# main_board_v0001.net
KiCad netlist of a schematic drawn in EAGLE
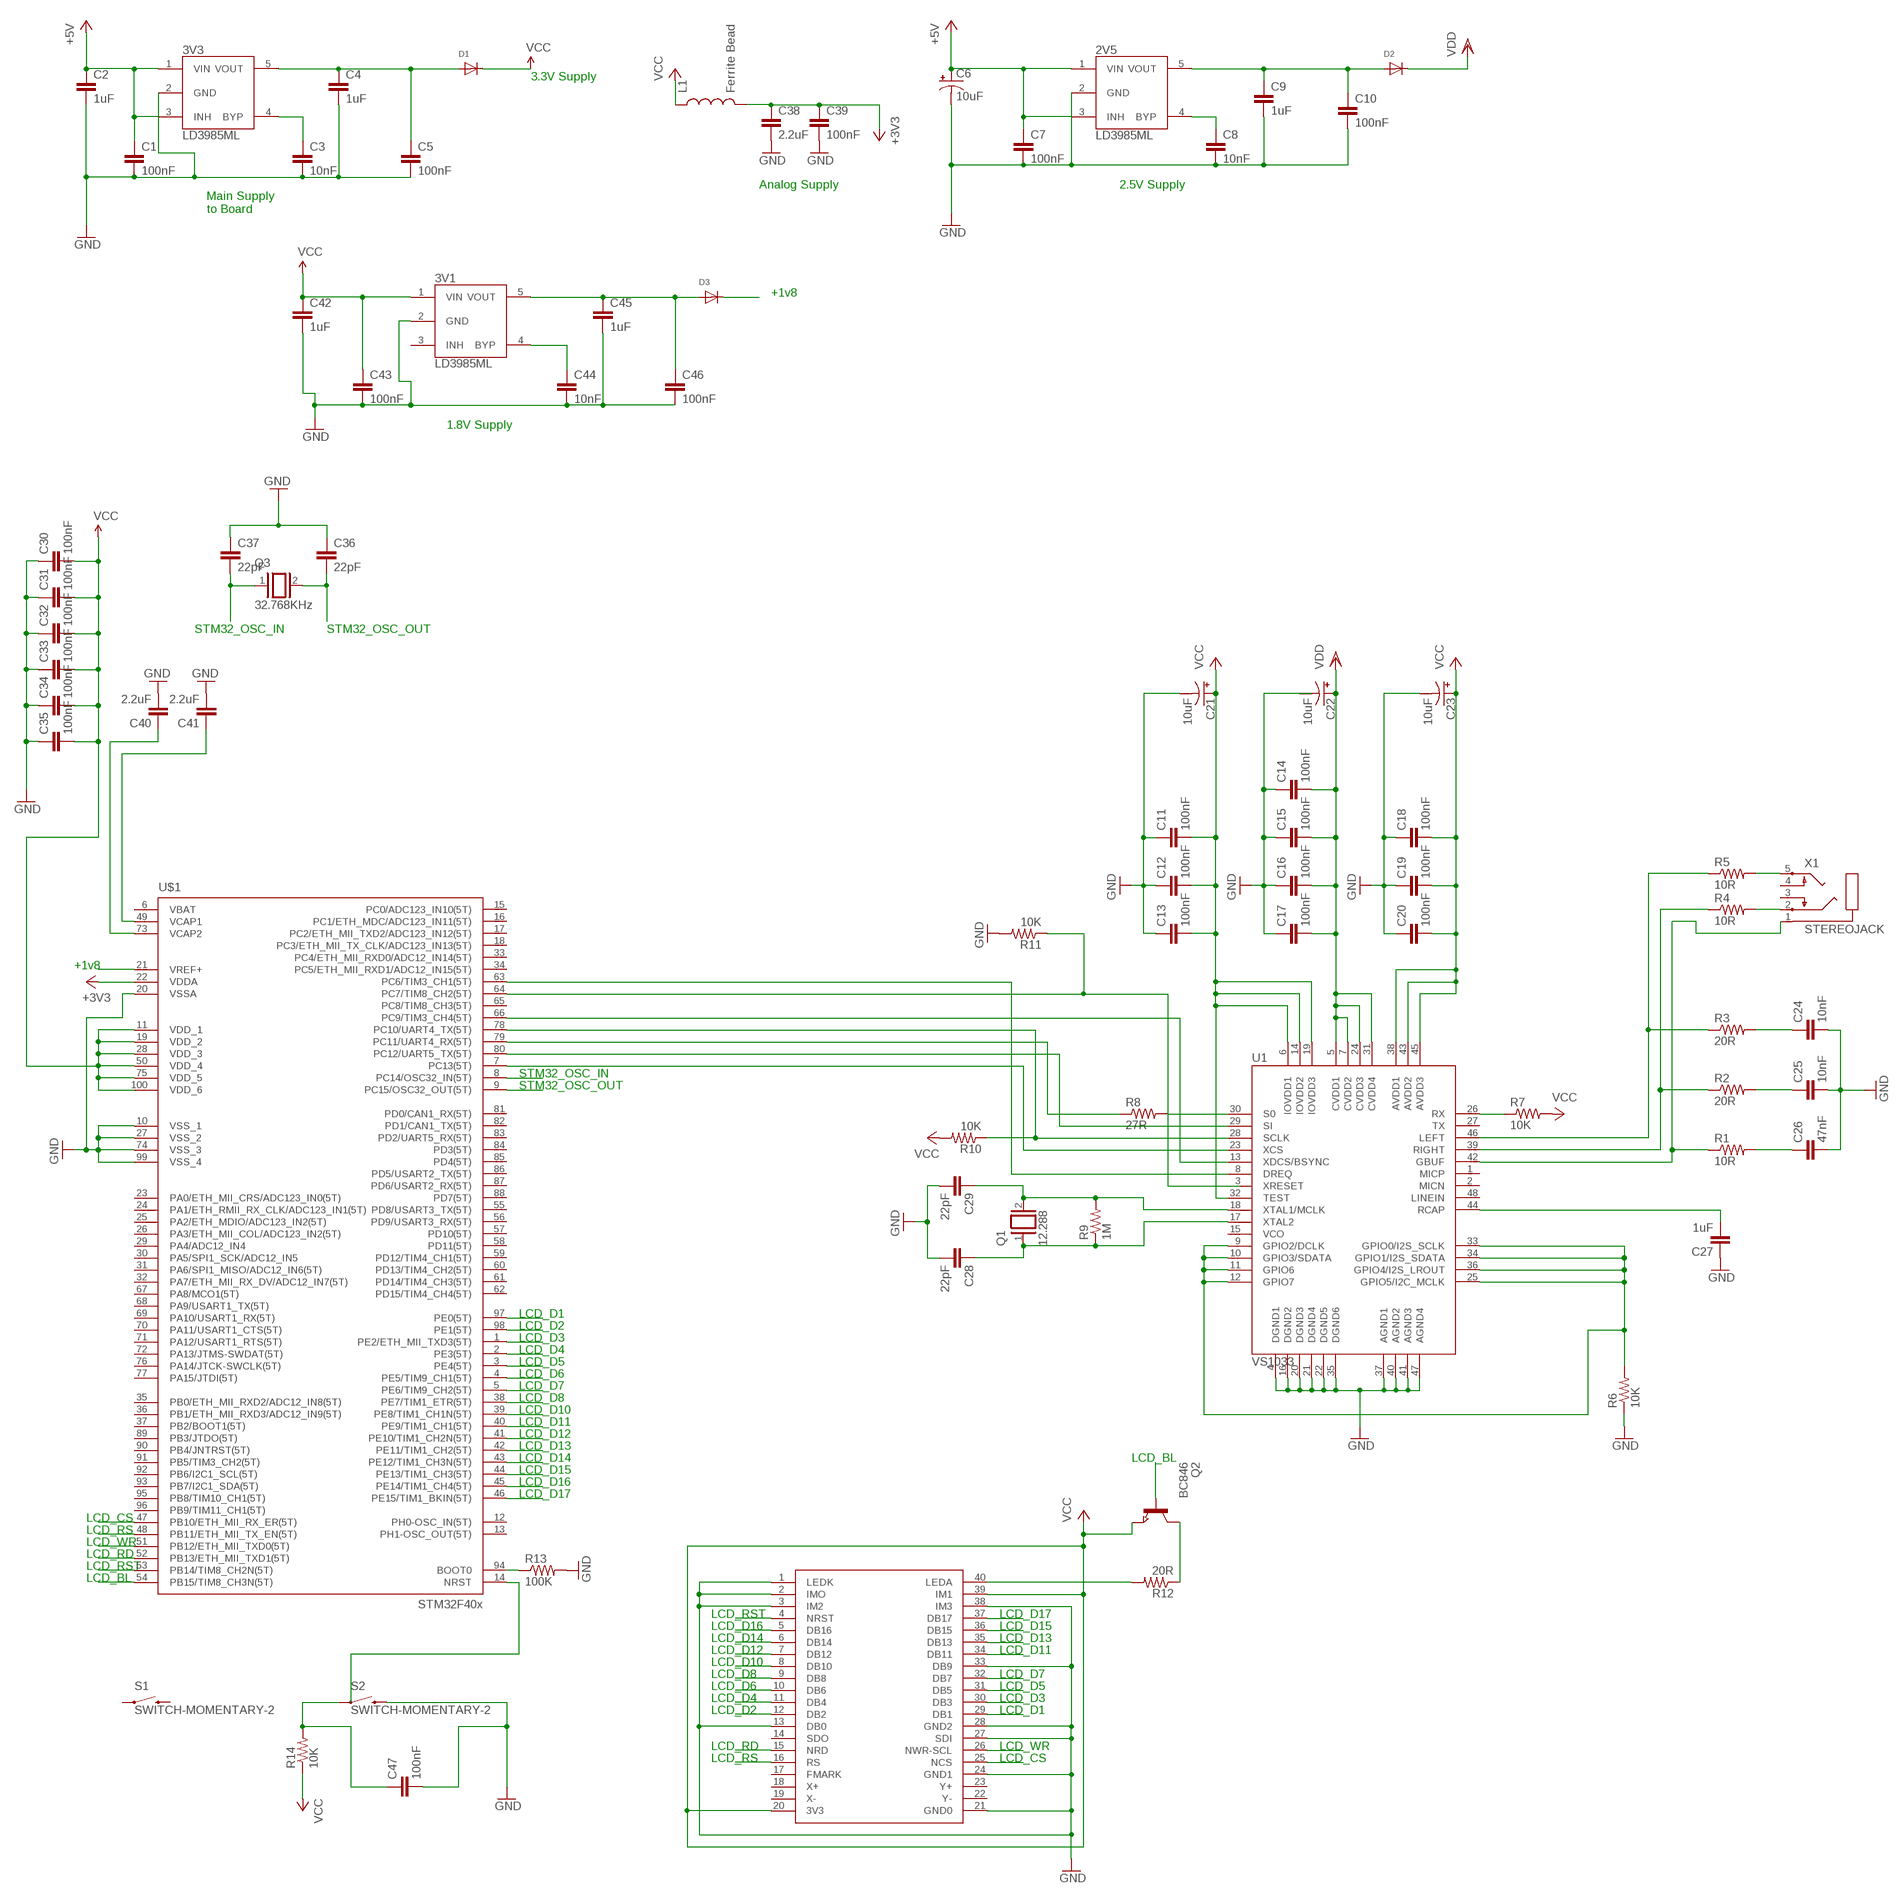
[diagram p0: schematic, sheet 1]

(export (version "E")
  (design (tool "Eeschema 10.0.6"))
  (components
    (comp (ref "2V5")
      (value "LD3985ML")
      (footprint "eagle-import:SOT-23-5L")
      (libsource (lib "eagle-import") (part "LD3985ML"))
    )
    (comp (ref "3V1")
      (value "LD3985ML")
      (footprint "eagle-import:SOT-23-5L")
      (libsource (lib "eagle-import") (part "LD3985ML"))
    )
    (comp (ref "3V3")
      (value "LD3985ML")
      (footprint "eagle-import:SOT-23-5L")
      (libsource (lib "eagle-import") (part "LD3985ML"))
    )
    (comp (ref "C1")
      (value "100nF")
      (footprint "eagle-import:C1005")
      (libsource (lib "eagle-import") (part "resistor_C-EUC1005"))
    )
    (comp (ref "C2")
      (value "1uF")
      (footprint "eagle-import:C0603")
      (libsource (lib "eagle-import") (part "C-EUC0603"))
    )
    (comp (ref "C3")
      (value "10nF")
      (footprint "eagle-import:C0603")
      (libsource (lib "eagle-import") (part "C-EUC0603"))
    )
    (comp (ref "C4")
      (value "1uF")
      (footprint "eagle-import:C0603")
      (libsource (lib "eagle-import") (part "C-EUC0603"))
    )
    (comp (ref "C5")
      (value "100nF")
      (footprint "eagle-import:C1005")
      (libsource (lib "eagle-import") (part "resistor_C-EUC1005"))
    )
    (comp (ref "C6")
      (value "10uF")
      (footprint "eagle-import:EIA3528-KIT")
      (libsource (lib "eagle-import") (part "CAP_POL3528-KIT"))
    )
    (comp (ref "C7")
      (value "100nF")
      (footprint "eagle-import:C1005")
      (libsource (lib "eagle-import") (part "resistor_C-EUC1005"))
    )
    (comp (ref "C8")
      (value "10nF")
      (footprint "eagle-import:C0603")
      (libsource (lib "eagle-import") (part "C-EUC0603"))
    )
    (comp (ref "C9")
      (value "1uF")
      (footprint "eagle-import:C0603")
      (libsource (lib "eagle-import") (part "C-EUC0603"))
    )
    (comp (ref "C10")
      (value "100nF")
      (footprint "eagle-import:C1005@1")
      (libsource (lib "eagle-import") (part "C-EUC1005"))
    )
    (comp (ref "C11")
      (value "100nF")
      (footprint "eagle-import:C0603")
      (libsource (lib "eagle-import") (part "C-EUC0603"))
    )
    (comp (ref "C12")
      (value "100nF")
      (footprint "eagle-import:C0603")
      (libsource (lib "eagle-import") (part "C-EUC0603"))
    )
    (comp (ref "C13")
      (value "100nF")
      (footprint "eagle-import:C0603")
      (libsource (lib "eagle-import") (part "C-EUC0603"))
    )
    (comp (ref "C14")
      (value "100nF")
      (footprint "eagle-import:C0603")
      (libsource (lib "eagle-import") (part "C-EUC0603"))
    )
    (comp (ref "C15")
      (value "100nF")
      (footprint "eagle-import:C0603")
      (libsource (lib "eagle-import") (part "C-EUC0603"))
    )
    (comp (ref "C16")
      (value "100nF")
      (footprint "eagle-import:C0603")
      (libsource (lib "eagle-import") (part "C-EUC0603"))
    )
    (comp (ref "C17")
      (value "100nF")
      (footprint "eagle-import:C0603")
      (libsource (lib "eagle-import") (part "C-EUC0603"))
    )
    (comp (ref "C18")
      (value "100nF")
      (footprint "eagle-import:C0603")
      (libsource (lib "eagle-import") (part "C-EUC0603"))
    )
    (comp (ref "C19")
      (value "100nF")
      (footprint "eagle-import:C0603")
      (libsource (lib "eagle-import") (part "C-EUC0603"))
    )
    (comp (ref "C20")
      (value "100nF")
      (footprint "eagle-import:C0603")
      (libsource (lib "eagle-import") (part "C-EUC0603"))
    )
    (comp (ref "C21")
      (value "10uF")
      (footprint "eagle-import:EIA3528-KIT")
      (libsource (lib "eagle-import") (part "CAP_POL3528-KIT"))
    )
    (comp (ref "C22")
      (value "10uF")
      (footprint "eagle-import:EIA3528-KIT")
      (libsource (lib "eagle-import") (part "CAP_POL3528-KIT"))
    )
    (comp (ref "C23")
      (value "10uF")
      (footprint "eagle-import:EIA3528-KIT")
      (libsource (lib "eagle-import") (part "CAP_POL3528-KIT"))
    )
    (comp (ref "C24")
      (value "10nF")
      (footprint "eagle-import:C0603")
      (libsource (lib "eagle-import") (part "C-EUC0603"))
    )
    (comp (ref "C25")
      (value "10nF")
      (footprint "eagle-import:C0603")
      (libsource (lib "eagle-import") (part "C-EUC0603"))
    )
    (comp (ref "C26")
      (value "47nF")
      (footprint "eagle-import:C0603")
      (libsource (lib "eagle-import") (part "C-EUC0603"))
    )
    (comp (ref "C27")
      (value "1uF")
      (footprint "eagle-import:C0603")
      (libsource (lib "eagle-import") (part "C-EUC0603"))
    )
    (comp (ref "C28")
      (value "22pF")
      (footprint "eagle-import:C0603")
      (libsource (lib "eagle-import") (part "C-EUC0603"))
    )
    (comp (ref "C29")
      (value "22pF")
      (footprint "eagle-import:C0603")
      (libsource (lib "eagle-import") (part "C-EUC0603"))
    )
    (comp (ref "C30")
      (value "100nF")
      (footprint "eagle-import:C1005")
      (libsource (lib "eagle-import") (part "resistor_C-EUC1005"))
    )
    (comp (ref "C31")
      (value "100nF")
      (footprint "eagle-import:C1005")
      (libsource (lib "eagle-import") (part "resistor_C-EUC1005"))
    )
    (comp (ref "C32")
      (value "100nF")
      (footprint "eagle-import:C1005")
      (libsource (lib "eagle-import") (part "resistor_C-EUC1005"))
    )
    (comp (ref "C33")
      (value "100nF")
      (footprint "eagle-import:C1005")
      (libsource (lib "eagle-import") (part "resistor_C-EUC1005"))
    )
    (comp (ref "C34")
      (value "100nF")
      (footprint "eagle-import:C1005")
      (libsource (lib "eagle-import") (part "resistor_C-EUC1005"))
    )
    (comp (ref "C35")
      (value "100nF")
      (footprint "eagle-import:C1005")
      (libsource (lib "eagle-import") (part "resistor_C-EUC1005"))
    )
    (comp (ref "C36")
      (value "22pF")
      (footprint "eagle-import:C1005")
      (libsource (lib "eagle-import") (part "resistor_C-EUC1005"))
    )
    (comp (ref "C37")
      (value "22pF")
      (footprint "eagle-import:C1005")
      (libsource (lib "eagle-import") (part "resistor_C-EUC1005"))
    )
    (comp (ref "C38")
      (value "2.2uF")
      (footprint "eagle-import:C1005")
      (libsource (lib "eagle-import") (part "resistor_C-EUC1005"))
    )
    (comp (ref "C39")
      (value "100nF")
      (footprint "eagle-import:C1005")
      (libsource (lib "eagle-import") (part "resistor_C-EUC1005"))
    )
    (comp (ref "C40")
      (value "2.2uF")
      (footprint "eagle-import:C1005")
      (libsource (lib "eagle-import") (part "resistor_C-EUC1005"))
    )
    (comp (ref "C41")
      (value "2.2uF")
      (footprint "eagle-import:C1005")
      (libsource (lib "eagle-import") (part "resistor_C-EUC1005"))
    )
    (comp (ref "C42")
      (value "1uF")
      (footprint "eagle-import:C0603")
      (libsource (lib "eagle-import") (part "C-EUC0603"))
    )
    (comp (ref "C43")
      (value "100nF")
      (footprint "eagle-import:C1005")
      (libsource (lib "eagle-import") (part "resistor_C-EUC1005"))
    )
    (comp (ref "C44")
      (value "10nF")
      (footprint "eagle-import:C0603")
      (libsource (lib "eagle-import") (part "C-EUC0603"))
    )
    (comp (ref "C45")
      (value "1uF")
      (footprint "eagle-import:C0603")
      (libsource (lib "eagle-import") (part "C-EUC0603"))
    )
    (comp (ref "C46")
      (value "100nF")
      (footprint "eagle-import:C1005")
      (libsource (lib "eagle-import") (part "resistor_C-EUC1005"))
    )
    (comp (ref "C47")
      (value "100nF")
      (footprint "eagle-import:C0603")
      (libsource (lib "eagle-import") (part "C-EUC0603"))
    )
    (comp (ref "D1")
      (value "DIODESOD-323F")
      (footprint "eagle-import:SOD-323F")
      (libsource (lib "eagle-import") (part "DIODESOD-323F"))
    )
    (comp (ref "D2")
      (value "DIODESOD-323F")
      (footprint "eagle-import:SOD-323F")
      (libsource (lib "eagle-import") (part "DIODESOD-323F"))
    )
    (comp (ref "D3")
      (value "DIODESOD-323F")
      (footprint "eagle-import:SOD-323F")
      (libsource (lib "eagle-import") (part "DIODESOD-323F"))
    )
    (comp (ref "L1")
      (value "Ferrite Bead")
      (footprint "eagle-import:C0402")
      (libsource (lib "eagle-import") (part "INDUCTOR0402"))
    )
    (comp (ref "Q1")
      (value "12.288")
      (footprint "eagle-import:QS")
      (libsource (lib "eagle-import") (part "XTAL/S"))
    )
    (comp (ref "Q2")
      (value "BC846")
      (footprint "eagle-import:SOT23")
      (libsource (lib "eagle-import") (part "NPN-TRANSISTOR_SOT23"))
    )
    (comp (ref "Q3")
      (value "32.768KHz")
      (footprint "eagle-import:QS")
      (libsource (lib "eagle-import") (part "XTAL/S"))
    )
    (comp (ref "R1")
      (value "10R")
      (footprint "eagle-import:M0805")
      (libsource (lib "eagle-import") (part "R-US_M0805"))
    )
    (comp (ref "R2")
      (value "20R")
      (footprint "eagle-import:M0805")
      (libsource (lib "eagle-import") (part "R-US_M0805"))
    )
    (comp (ref "R3")
      (value "20R")
      (footprint "eagle-import:M0805")
      (libsource (lib "eagle-import") (part "R-US_M0805"))
    )
    (comp (ref "R4")
      (value "10R")
      (footprint "eagle-import:M0805")
      (libsource (lib "eagle-import") (part "R-US_M0805"))
    )
    (comp (ref "R5")
      (value "10R")
      (footprint "eagle-import:M0805")
      (libsource (lib "eagle-import") (part "R-US_M0805"))
    )
    (comp (ref "R6")
      (value "10K")
      (footprint "eagle-import:M0805")
      (libsource (lib "eagle-import") (part "R-US_M0805"))
    )
    (comp (ref "R7")
      (value "10K")
      (footprint "eagle-import:M0805")
      (libsource (lib "eagle-import") (part "R-US_M0805"))
    )
    (comp (ref "R8")
      (value "27R")
      (footprint "eagle-import:M0805")
      (libsource (lib "eagle-import") (part "R-US_M0805"))
    )
    (comp (ref "R9")
      (value "1M")
      (footprint "eagle-import:M0805")
      (libsource (lib "eagle-import") (part "R-US_M0805"))
    )
    (comp (ref "R10")
      (value "10K")
      (footprint "eagle-import:M0805")
      (libsource (lib "eagle-import") (part "R-US_M0805"))
    )
    (comp (ref "R11")
      (value "10K")
      (footprint "eagle-import:M0805")
      (libsource (lib "eagle-import") (part "R-US_M0805"))
    )
    (comp (ref "R12")
      (value "20R")
      (footprint "eagle-import:M0805")
      (libsource (lib "eagle-import") (part "R-US_M0805"))
    )
    (comp (ref "R13")
      (value "100K")
      (footprint "eagle-import:M0805")
      (libsource (lib "eagle-import") (part "R-US_M0805"))
    )
    (comp (ref "R14")
      (value "10K")
      (footprint "eagle-import:M0805")
      (libsource (lib "eagle-import") (part "R-US_M0805"))
    )
    (comp (ref "S1")
      (value "SWITCH-MOMENTARY-2")
      (footprint "eagle-import:TACTILE_SWITCH_TALL")
      (libsource (lib "eagle-import") (part "SWITCH-MOMENTARY-2"))
    )
    (comp (ref "S2")
      (value "SWITCH-MOMENTARY-2")
      (footprint "eagle-import:TACTILE_SWITCH_TALL")
      (libsource (lib "eagle-import") (part "SWITCH-MOMENTARY-2"))
    )
    (comp (ref "U$1")
      (value "STM32F407V")
      (footprint "eagle-import:TQFP100")
      (libsource (lib "eagle-import") (part "STM32F407V"))
    )
    (comp (ref "U$2")
      (value "MIKROE-PROTO-ILI9341")
      (footprint "eagle-import:2X20-PINHEAD")
      (libsource (lib "eagle-import") (part "MIKROE-PROTO-ILI9341"))
    )
    (comp (ref "U1")
      (value "VS1033")
      (footprint "eagle-import:LQFP-48")
      (libsource (lib "eagle-import") (part "VS1033"))
    )
    (comp (ref "X1")
      (value "STEREOJACK")
      (footprint "eagle-import:STX3100")
      (libsource (lib "eagle-import") (part "STEREOJACK"))
    )
  )
  (nets
    (net (code "1") (name "+3V3") (class "Default")
      (node (ref "C38") (pin "1") (pinfunction "1_1") (pintype "passive"))
      (node (ref "C39") (pin "1") (pinfunction "1_1") (pintype "passive"))
      (node (ref "L1") (pin "2") (pinfunction "2_2") (pintype "passive"))
      (node (ref "U$1") (pin "22") (pinfunction "VDDA_22") (pintype "bidirectional"))
    )
    (net (code "2") (name "+5V") (class "Default")
      (node (ref "2V5") (pin "1") (pinfunction "VIN_1") (pintype "bidirectional"))
      (node (ref "2V5") (pin "3") (pinfunction "INH_3") (pintype "bidirectional"))
      (node (ref "3V3") (pin "1") (pinfunction "VIN_1") (pintype "bidirectional"))
      (node (ref "3V3") (pin "3") (pinfunction "INH_3") (pintype "bidirectional"))
      (node (ref "C1") (pin "1") (pinfunction "1_1") (pintype "passive"))
      (node (ref "C2") (pin "1") (pinfunction "1_1") (pintype "passive"))
      (node (ref "C6") (pin "A") (pinfunction "+_A") (pintype "passive"))
      (node (ref "C7") (pin "1") (pinfunction "1_1") (pintype "passive"))
    )
    (net (code "3") (name "/+1V8") (class "Default")
      (node (ref "D3") (pin "C") (pinfunction "C_C") (pintype "passive"))
      (node (ref "U$1") (pin "21") (pinfunction "VREF+_21") (pintype "bidirectional"))
    )
    (net (code "4") (name "/LCD_BL") (class "Default")
      (node (ref "Q2") (pin "1") (pinfunction "B_1") (pintype "passive"))
      (node (ref "U$1") (pin "54") (pinfunction "PB15/TIM8_CH3N(5T)_54") (pintype "bidirectional"))
    )
    (net (code "5") (name "/LCD_CS") (class "Default")
      (node (ref "U$1") (pin "47") (pinfunction "PB10/ETH_MII_RX_ER(5T)_47") (pintype "bidirectional"))
      (node (ref "U$2") (pin "25") (pinfunction "NCS_25") (pintype "bidirectional"))
    )
    (net (code "6") (name "/LCD_D1") (class "Default")
      (node (ref "U$1") (pin "97") (pinfunction "PE0(5T)_97") (pintype "bidirectional"))
      (node (ref "U$2") (pin "29") (pinfunction "DB1_29") (pintype "bidirectional"))
    )
    (net (code "7") (name "/LCD_D2") (class "Default")
      (node (ref "U$1") (pin "98") (pinfunction "PE1(5T)_98") (pintype "bidirectional"))
      (node (ref "U$2") (pin "12") (pinfunction "DB2_12") (pintype "bidirectional"))
    )
    (net (code "8") (name "/LCD_D3") (class "Default")
      (node (ref "U$1") (pin "1") (pinfunction "PE2/ETH_MII_TXD3(5T)_1") (pintype "bidirectional"))
      (node (ref "U$2") (pin "30") (pinfunction "DB3_30") (pintype "bidirectional"))
    )
    (net (code "9") (name "/LCD_D4") (class "Default")
      (node (ref "U$1") (pin "2") (pinfunction "PE3(5T)_2") (pintype "bidirectional"))
      (node (ref "U$2") (pin "11") (pinfunction "DB4_11") (pintype "bidirectional"))
    )
    (net (code "10") (name "/LCD_D5") (class "Default")
      (node (ref "U$1") (pin "3") (pinfunction "PE4(5T)_3") (pintype "bidirectional"))
      (node (ref "U$2") (pin "31") (pinfunction "DB5_31") (pintype "bidirectional"))
    )
    (net (code "11") (name "/LCD_D6") (class "Default")
      (node (ref "U$1") (pin "4") (pinfunction "PE5/TIM9_CH1(5T)_4") (pintype "bidirectional"))
      (node (ref "U$2") (pin "10") (pinfunction "DB6_10") (pintype "bidirectional"))
    )
    (net (code "12") (name "/LCD_D7") (class "Default")
      (node (ref "U$1") (pin "5") (pinfunction "PE6/TIM9_CH2(5T)_5") (pintype "bidirectional"))
      (node (ref "U$2") (pin "32") (pinfunction "DB7_32") (pintype "bidirectional"))
    )
    (net (code "13") (name "/LCD_D8") (class "Default")
      (node (ref "U$1") (pin "38") (pinfunction "PE7/TIM1_ETR(5T)_38") (pintype "bidirectional"))
      (node (ref "U$2") (pin "9") (pinfunction "DB8_9") (pintype "bidirectional"))
    )
    (net (code "14") (name "/LCD_D10") (class "Default")
      (node (ref "U$1") (pin "39") (pinfunction "PE8/TIM1_CH1N(5T)_39") (pintype "bidirectional"))
      (node (ref "U$2") (pin "8") (pinfunction "DB10_8") (pintype "bidirectional"))
    )
    (net (code "15") (name "/LCD_D11") (class "Default")
      (node (ref "U$1") (pin "40") (pinfunction "PE9/TIM1_CH1(5T)_40") (pintype "bidirectional"))
      (node (ref "U$2") (pin "34") (pinfunction "DB11_34") (pintype "bidirectional"))
    )
    (net (code "16") (name "/LCD_D12") (class "Default")
      (node (ref "U$1") (pin "41") (pinfunction "PE10/TIM1_CH2N(5T)_41") (pintype "bidirectional"))
      (node (ref "U$2") (pin "7") (pinfunction "DB12_7") (pintype "bidirectional"))
    )
    (net (code "17") (name "/LCD_D13") (class "Default")
      (node (ref "U$1") (pin "42") (pinfunction "PE11/TIM1_CH2(5T)_42") (pintype "bidirectional"))
      (node (ref "U$2") (pin "35") (pinfunction "DB13_35") (pintype "bidirectional"))
    )
    (net (code "18") (name "/LCD_D14") (class "Default")
      (node (ref "U$1") (pin "43") (pinfunction "PE12/TIM1_CH3N(5T)_43") (pintype "bidirectional"))
      (node (ref "U$2") (pin "6") (pinfunction "DB14_6") (pintype "bidirectional"))
    )
    (net (code "19") (name "/LCD_D15") (class "Default")
      (node (ref "U$1") (pin "44") (pinfunction "PE13/TIM1_CH3(5T)_44") (pintype "bidirectional"))
      (node (ref "U$2") (pin "36") (pinfunction "DB15_36") (pintype "bidirectional"))
    )
    (net (code "20") (name "/LCD_D16") (class "Default")
      (node (ref "U$1") (pin "45") (pinfunction "PE14/TIM1_CH4(5T)_45") (pintype "bidirectional"))
      (node (ref "U$2") (pin "5") (pinfunction "DB16_5") (pintype "bidirectional"))
    )
    (net (code "21") (name "/LCD_D17") (class "Default")
      (node (ref "U$1") (pin "46") (pinfunction "PE15/TIM1_BKIN(5T)_46") (pintype "bidirectional"))
      (node (ref "U$2") (pin "37") (pinfunction "DB17_37") (pintype "bidirectional"))
    )
    (net (code "22") (name "/LCD_RD") (class "Default")
      (node (ref "U$1") (pin "52") (pinfunction "PB13/ETH_MII_TXD1(5T)_52") (pintype "bidirectional"))
      (node (ref "U$2") (pin "15") (pinfunction "NRD_15") (pintype "bidirectional"))
    )
    (net (code "23") (name "/LCD_RS") (class "Default")
      (node (ref "U$1") (pin "48") (pinfunction "PB11/ETH_MII_TX_EN(5T)_48") (pintype "bidirectional"))
      (node (ref "U$2") (pin "16") (pinfunction "RS_16") (pintype "bidirectional"))
    )
    (net (code "24") (name "/LCD_RST") (class "Default")
      (node (ref "U$1") (pin "53") (pinfunction "PB14/TIM8_CH2N(5T)_53") (pintype "bidirectional"))
      (node (ref "U$2") (pin "4") (pinfunction "NRST_4") (pintype "bidirectional"))
    )
    (net (code "25") (name "/LCD_WR") (class "Default")
      (node (ref "U$1") (pin "51") (pinfunction "PB12/ETH_MII_TXD0(5T)_51") (pintype "bidirectional"))
      (node (ref "U$2") (pin "26") (pinfunction "NWR-SCL_26") (pintype "bidirectional"))
    )
    (net (code "26") (name "/STM32_OSC_IN") (class "Default")
      (node (ref "C37") (pin "2") (pinfunction "2_2") (pintype "passive"))
      (node (ref "Q3") (pin "1") (pinfunction "1_1") (pintype "passive"))
      (node (ref "U$1") (pin "8") (pinfunction "PC14/OSC32_IN(5T)_8") (pintype "bidirectional"))
    )
    (net (code "27") (name "/STM32_OSC_OUT") (class "Default")
      (node (ref "C36") (pin "2") (pinfunction "2_2") (pintype "passive"))
      (node (ref "Q3") (pin "2") (pinfunction "2_2") (pintype "passive"))
      (node (ref "U$1") (pin "9") (pinfunction "PC15/OSC32_OUT(5T)_9") (pintype "bidirectional"))
    )
    (net (code "28") (name "GND") (class "Default")
      (node (ref "2V5") (pin "2") (pinfunction "GND_2") (pintype "bidirectional"))
      (node (ref "3V1") (pin "2") (pinfunction "GND_2") (pintype "bidirectional"))
      (node (ref "3V3") (pin "2") (pinfunction "GND_2") (pintype "bidirectional"))
      (node (ref "C1") (pin "2") (pinfunction "2_2") (pintype "passive"))
      (node (ref "C10") (pin "2") (pinfunction "2_2") (pintype "passive"))
      (node (ref "C11") (pin "1") (pinfunction "1_1") (pintype "passive"))
      (node (ref "C12") (pin "1") (pinfunction "1_1") (pintype "passive"))
      (node (ref "C13") (pin "1") (pinfunction "1_1") (pintype "passive"))
      (node (ref "C14") (pin "1") (pinfunction "1_1") (pintype "passive"))
      (node (ref "C15") (pin "1") (pinfunction "1_1") (pintype "passive"))
      (node (ref "C16") (pin "1") (pinfunction "1_1") (pintype "passive"))
      (node (ref "C17") (pin "1") (pinfunction "1_1") (pintype "passive"))
      (node (ref "C18") (pin "1") (pinfunction "1_1") (pintype "passive"))
      (node (ref "C19") (pin "1") (pinfunction "1_1") (pintype "passive"))
      (node (ref "C2") (pin "2") (pinfunction "2_2") (pintype "passive"))
      (node (ref "C20") (pin "1") (pinfunction "1_1") (pintype "passive"))
      (node (ref "C21") (pin "C") (pinfunction "-_C") (pintype "passive"))
      (node (ref "C23") (pin "C") (pinfunction "-_C") (pintype "passive"))
      (node (ref "C24") (pin "2") (pinfunction "2_2") (pintype "passive"))
      (node (ref "C25") (pin "2") (pinfunction "2_2") (pintype "passive"))
      (node (ref "C26") (pin "2") (pinfunction "2_2") (pintype "passive"))
      (node (ref "C27") (pin "1") (pinfunction "1_1") (pintype "passive"))
      (node (ref "C28") (pin "2") (pinfunction "2_2") (pintype "passive"))
      (node (ref "C29") (pin "2") (pinfunction "2_2") (pintype "passive"))
      (node (ref "C3") (pin "2") (pinfunction "2_2") (pintype "passive"))
      (node (ref "C30") (pin "1") (pinfunction "1_1") (pintype "passive"))
      (node (ref "C31") (pin "1") (pinfunction "1_1") (pintype "passive"))
      (node (ref "C32") (pin "1") (pinfunction "1_1") (pintype "passive"))
      (node (ref "C33") (pin "1") (pinfunction "1_1") (pintype "passive"))
      (node (ref "C34") (pin "1") (pinfunction "1_1") (pintype "passive"))
      (node (ref "C35") (pin "1") (pinfunction "1_1") (pintype "passive"))
      (node (ref "C36") (pin "1") (pinfunction "1_1") (pintype "passive"))
      (node (ref "C37") (pin "1") (pinfunction "1_1") (pintype "passive"))
      (node (ref "C38") (pin "2") (pinfunction "2_2") (pintype "passive"))
      (node (ref "C39") (pin "2") (pinfunction "2_2") (pintype "passive"))
      (node (ref "C4") (pin "2") (pinfunction "2_2") (pintype "passive"))
      (node (ref "C40") (pin "2") (pinfunction "2_2") (pintype "passive"))
      (node (ref "C41") (pin "2") (pinfunction "2_2") (pintype "passive"))
      (node (ref "C42") (pin "2") (pinfunction "2_2") (pintype "passive"))
      (node (ref "C43") (pin "2") (pinfunction "2_2") (pintype "passive"))
      (node (ref "C44") (pin "2") (pinfunction "2_2") (pintype "passive"))
      (node (ref "C45") (pin "2") (pinfunction "2_2") (pintype "passive"))
      (node (ref "C46") (pin "2") (pinfunction "2_2") (pintype "passive"))
      (node (ref "C47") (pin "2") (pinfunction "2_2") (pintype "passive"))
      (node (ref "C5") (pin "2") (pinfunction "2_2") (pintype "passive"))
      (node (ref "C6") (pin "C") (pinfunction "-_C") (pintype "passive"))
      (node (ref "C7") (pin "2") (pinfunction "2_2") (pintype "passive"))
      (node (ref "C8") (pin "2") (pinfunction "2_2") (pintype "passive"))
      (node (ref "C9") (pin "2") (pinfunction "2_2") (pintype "passive"))
      (node (ref "R11") (pin "2") (pinfunction "2_2") (pintype "passive"))
      (node (ref "R13") (pin "2") (pinfunction "2_2") (pintype "passive"))
      (node (ref "R6") (pin "1") (pinfunction "1_1") (pintype "passive"))
      (node (ref "S2") (pin "B2") (pinfunction "2_B2") (pintype "passive"))
      (node (ref "U$1") (pin "10") (pinfunction "VSS_1_10") (pintype "bidirectional"))
      (node (ref "U$1") (pin "20") (pinfunction "VSSA_20") (pintype "bidirectional"))
      (node (ref "U$1") (pin "27") (pinfunction "VSS_2_27") (pintype "bidirectional"))
      (node (ref "U$1") (pin "74") (pinfunction "VSS_3_74") (pintype "bidirectional"))
      (node (ref "U$1") (pin "99") (pinfunction "VSS_4_99") (pintype "bidirectional"))
      (node (ref "U$2") (pin "1") (pinfunction "LEDK_1") (pintype "bidirectional"))
      (node (ref "U$2") (pin "13") (pinfunction "DB0_13") (pintype "bidirectional"))
      (node (ref "U$2") (pin "2") (pinfunction "IMO_2") (pintype "bidirectional"))
      (node (ref "U$2") (pin "21") (pinfunction "GND0_21") (pintype "bidirectional"))
      (node (ref "U$2") (pin "24") (pinfunction "GND1_24") (pintype "bidirectional"))
      (node (ref "U$2") (pin "27") (pinfunction "SDI_27") (pintype "bidirectional"))
      (node (ref "U$2") (pin "28") (pinfunction "GND2_28") (pintype "bidirectional"))
      (node (ref "U$2") (pin "3") (pinfunction "IM2_3") (pintype "bidirectional"))
      (node (ref "U$2") (pin "33") (pinfunction "DB9_33") (pintype "bidirectional"))
      (node (ref "U$2") (pin "38") (pinfunction "IM3_38") (pintype "bidirectional"))
      (node (ref "U1") (pin "16") (pinfunction "DGND2_16") (pintype "bidirectional"))
      (node (ref "U1") (pin "20") (pinfunction "DGND3_20") (pintype "bidirectional"))
      (node (ref "U1") (pin "21") (pinfunction "DGND4_21") (pintype "bidirectional"))
      (node (ref "U1") (pin "22") (pinfunction "DGND5_22") (pintype "bidirectional"))
      (node (ref "U1") (pin "35") (pinfunction "DGND6_35") (pintype "bidirectional"))
      (node (ref "U1") (pin "37") (pinfunction "AGND1_37") (pintype "bidirectional"))
      (node (ref "U1") (pin "4") (pinfunction "DGND1_4") (pintype "bidirectional"))
      (node (ref "U1") (pin "40") (pinfunction "AGND2_40") (pintype "bidirectional"))
      (node (ref "U1") (pin "41") (pinfunction "AGND3_41") (pintype "bidirectional"))
      (node (ref "U1") (pin "47") (pinfunction "AGND4_47") (pintype "bidirectional"))
    )
    (net (code "29") (name "Net-(2V5-BYP)") (class "Default")
      (node (ref "2V5") (pin "4") (pinfunction "BYP_4") (pintype "bidirectional"))
      (node (ref "C8") (pin "1") (pinfunction "1_1") (pintype "passive"))
    )
    (net (code "30") (name "Net-(2V5-VOUT)") (class "Default")
      (node (ref "2V5") (pin "5") (pinfunction "VOUT_5") (pintype "bidirectional"))
      (node (ref "C10") (pin "1") (pinfunction "1_1") (pintype "passive"))
      (node (ref "C9") (pin "1") (pinfunction "1_1") (pintype "passive"))
      (node (ref "D2") (pin "A") (pinfunction "A_A") (pintype "passive"))
    )
    (net (code "31") (name "Net-(3V1-BYP)") (class "Default")
      (node (ref "3V1") (pin "4") (pinfunction "BYP_4") (pintype "bidirectional"))
      (node (ref "C44") (pin "1") (pinfunction "1_1") (pintype "passive"))
    )
    (net (code "32") (name "Net-(3V1-VOUT)") (class "Default")
      (node (ref "3V1") (pin "5") (pinfunction "VOUT_5") (pintype "bidirectional"))
      (node (ref "C45") (pin "1") (pinfunction "1_1") (pintype "passive"))
      (node (ref "C46") (pin "1") (pinfunction "1_1") (pintype "passive"))
      (node (ref "D3") (pin "A") (pinfunction "A_A") (pintype "passive"))
    )
    (net (code "33") (name "Net-(3V3-BYP)") (class "Default")
      (node (ref "3V3") (pin "4") (pinfunction "BYP_4") (pintype "bidirectional"))
      (node (ref "C3") (pin "1") (pinfunction "1_1") (pintype "passive"))
    )
    (net (code "34") (name "Net-(3V3-VOUT)") (class "Default")
      (node (ref "3V3") (pin "5") (pinfunction "VOUT_5") (pintype "bidirectional"))
      (node (ref "C4") (pin "1") (pinfunction "1_1") (pintype "passive"))
      (node (ref "C5") (pin "1") (pinfunction "1_1") (pintype "passive"))
      (node (ref "D1") (pin "A") (pinfunction "A_A") (pintype "passive"))
    )
    (net (code "35") (name "Net-(C24-Pad1)") (class "Default")
      (node (ref "C24") (pin "1") (pinfunction "1_1") (pintype "passive"))
      (node (ref "R3") (pin "2") (pinfunction "2_2") (pintype "passive"))
    )
    (net (code "36") (name "Net-(C25-Pad1)") (class "Default")
      (node (ref "C25") (pin "1") (pinfunction "1_1") (pintype "passive"))
      (node (ref "R2") (pin "2") (pinfunction "2_2") (pintype "passive"))
    )
    (net (code "37") (name "Net-(C26-Pad1)") (class "Default")
      (node (ref "C26") (pin "1") (pinfunction "1_1") (pintype "passive"))
      (node (ref "R1") (pin "2") (pinfunction "2_2") (pintype "passive"))
    )
    (net (code "38") (name "Net-(Q2-C)") (class "Default")
      (node (ref "Q2") (pin "3") (pinfunction "C_3") (pintype "passive"))
      (node (ref "R12") (pin "1") (pinfunction "1_1") (pintype "passive"))
    )
    (net (code "39") (name "Net-(R4-Pad2)") (class "Default")
      (node (ref "R4") (pin "2") (pinfunction "2_2") (pintype "passive"))
      (node (ref "X1") (pin "2") (pinfunction "2_2") (pintype "passive"))
    )
    (net (code "40") (name "Net-(R5-Pad2)") (class "Default")
      (node (ref "R5") (pin "2") (pinfunction "2_2") (pintype "passive"))
      (node (ref "X1") (pin "5") (pinfunction "5_5") (pintype "passive"))
    )
    (net (code "41") (name "Net-(S2-1)") (class "Default")
      (node (ref "C47") (pin "1") (pinfunction "1_1") (pintype "passive"))
      (node (ref "R14") (pin "2") (pinfunction "2_2") (pintype "passive"))
      (node (ref "S2") (pin "A2") (pinfunction "1_A2") (pintype "passive"))
    )
    (net (code "42") (name "Net-(U$1-BOOT0)") (class "Default")
      (node (ref "R13") (pin "1") (pinfunction "1_1") (pintype "passive"))
      (node (ref "U$1") (pin "94") (pinfunction "BOOT0_94") (pintype "bidirectional"))
    )
    (net (code "43") (name "Net-(U$1-PC6{slash}TIM3_CH1(5T))") (class "Default")
      (node (ref "U$1") (pin "63") (pinfunction "PC6/TIM3_CH1(5T)_63") (pintype "bidirectional"))
      (node (ref "U1") (pin "8") (pinfunction "DREQ_8") (pintype "bidirectional"))
    )
    (net (code "44") (name "Net-(U$1-PC7{slash}TIM8_CH2(5T))") (class "Default")
      (node (ref "R11") (pin "1") (pinfunction "1_1") (pintype "passive"))
      (node (ref "U$1") (pin "64") (pinfunction "PC7/TIM8_CH2(5T)_64") (pintype "bidirectional"))
    )
    (net (code "45") (name "Net-(U$1-PC9{slash}TIM3_CH4(5T))") (class "Default")
      (node (ref "U$1") (pin "66") (pinfunction "PC9/TIM3_CH4(5T)_66") (pintype "bidirectional"))
      (node (ref "U1") (pin "13") (pinfunction "XDCS/BSYNC_13") (pintype "bidirectional"))
    )
    (net (code "46") (name "Net-(U$1-PC10{slash}UART4_TX(5T))") (class "Default")
      (node (ref "R10") (pin "1") (pinfunction "1_1") (pintype "passive"))
      (node (ref "U$1") (pin "78") (pinfunction "PC10/UART4_TX(5T)_78") (pintype "bidirectional"))
      (node (ref "U1") (pin "28") (pinfunction "SCLK_28") (pintype "bidirectional"))
    )
    (net (code "47") (name "Net-(U$1-PC11{slash}UART4_RX(5T))") (class "Default")
      (node (ref "R8") (pin "1") (pinfunction "1_1") (pintype "passive"))
      (node (ref "U$1") (pin "79") (pinfunction "PC11/UART4_RX(5T)_79") (pintype "bidirectional"))
    )
    (net (code "48") (name "Net-(U$1-PC12{slash}UART5_TX(5T))") (class "Default")
      (node (ref "U$1") (pin "80") (pinfunction "PC12/UART5_TX(5T)_80") (pintype "bidirectional"))
      (node (ref "U1") (pin "29") (pinfunction "SI_29") (pintype "bidirectional"))
    )
    (net (code "49") (name "Net-(U$1-PC13(5T))") (class "Default")
      (node (ref "U$1") (pin "7") (pinfunction "PC13(5T)_7") (pintype "bidirectional"))
      (node (ref "U1") (pin "23") (pinfunction "XCS_23") (pintype "bidirectional"))
    )
    (net (code "50") (name "Net-(U$1-VCAP1)") (class "Default")
      (node (ref "C41") (pin "1") (pinfunction "1_1") (pintype "passive"))
      (node (ref "U$1") (pin "49") (pinfunction "VCAP1_49") (pintype "bidirectional"))
    )
    (net (code "51") (name "Net-(U$1-VCAP2)") (class "Default")
      (node (ref "C40") (pin "1") (pinfunction "1_1") (pintype "passive"))
      (node (ref "U$1") (pin "73") (pinfunction "VCAP2_73") (pintype "bidirectional"))
    )
    (net (code "52") (name "Net-(U$2-LEDA)") (class "Default")
      (node (ref "R12") (pin "2") (pinfunction "2_2") (pintype "passive"))
      (node (ref "U$2") (pin "40") (pinfunction "LEDA_40") (pintype "bidirectional"))
    )
    (net (code "53") (name "Net-(U1-GBUF)") (class "Default")
      (node (ref "R1") (pin "1") (pinfunction "1_1") (pintype "passive"))
      (node (ref "U1") (pin "42") (pinfunction "GBUF_42") (pintype "bidirectional"))
      (node (ref "X1") (pin "1") (pinfunction "1_1") (pintype "passive"))
    )
    (net (code "54") (name "Net-(U1-GPIO0{slash}I2S_SCLK)") (class "Default")
      (node (ref "R6") (pin "2") (pinfunction "2_2") (pintype "passive"))
      (node (ref "U1") (pin "10") (pinfunction "GPIO3/SDATA_10") (pintype "bidirectional"))
      (node (ref "U1") (pin "11") (pinfunction "GPIO6_11") (pintype "bidirectional"))
      (node (ref "U1") (pin "12") (pinfunction "GPIO7_12") (pintype "bidirectional"))
      (node (ref "U1") (pin "25") (pinfunction "GPIO5/I2C_MCLK_25") (pintype "bidirectional"))
      (node (ref "U1") (pin "33") (pinfunction "GPIO0/I2S_SCLK_33") (pintype "bidirectional"))
      (node (ref "U1") (pin "34") (pinfunction "GPIO1/I2S_SDATA_34") (pintype "bidirectional"))
      (node (ref "U1") (pin "36") (pinfunction "GPIO4/I2S_LROUT_36") (pintype "bidirectional"))
      (node (ref "U1") (pin "9") (pinfunction "GPIO2/DCLK_9") (pintype "bidirectional"))
    )
    (net (code "55") (name "Net-(U1-LEFT)") (class "Default")
      (node (ref "R3") (pin "1") (pinfunction "1_1") (pintype "passive"))
      (node (ref "R5") (pin "1") (pinfunction "1_1") (pintype "passive"))
      (node (ref "U1") (pin "46") (pinfunction "LEFT_46") (pintype "bidirectional"))
    )
    (net (code "56") (name "Net-(U1-RCAP)") (class "Default")
      (node (ref "C27") (pin "2") (pinfunction "2_2") (pintype "passive"))
      (node (ref "U1") (pin "44") (pinfunction "RCAP_44") (pintype "bidirectional"))
    )
    (net (code "57") (name "Net-(U1-RIGHT)") (class "Default")
      (node (ref "R2") (pin "1") (pinfunction "1_1") (pintype "passive"))
      (node (ref "R4") (pin "1") (pinfunction "1_1") (pintype "passive"))
      (node (ref "U1") (pin "39") (pinfunction "RIGHT_39") (pintype "bidirectional"))
    )
    (net (code "58") (name "Net-(U1-RX)") (class "Default")
      (node (ref "R7") (pin "1") (pinfunction "1_1") (pintype "passive"))
      (node (ref "U1") (pin "26") (pinfunction "RX_26") (pintype "bidirectional"))
    )
    (net (code "59") (name "Net-(U1-S0)") (class "Default")
      (node (ref "R8") (pin "2") (pinfunction "2_2") (pintype "passive"))
      (node (ref "U1") (pin "30") (pinfunction "S0_30") (pintype "bidirectional"))
    )
    (net (code "60") (name "Net-(U1-XTAL1{slash}MCLK)") (class "Default")
      (node (ref "C29") (pin "1") (pinfunction "1_1") (pintype "passive"))
      (node (ref "Q1") (pin "2") (pinfunction "2_2") (pintype "passive"))
      (node (ref "R9") (pin "2") (pinfunction "2_2") (pintype "passive"))
      (node (ref "U1") (pin "18") (pinfunction "XTAL1/MCLK_18") (pintype "bidirectional"))
    )
    (net (code "61") (name "Net-(U1-XTAL2)") (class "Default")
      (node (ref "C28") (pin "1") (pinfunction "1_1") (pintype "passive"))
      (node (ref "Q1") (pin "1") (pinfunction "1_1") (pintype "passive"))
      (node (ref "R9") (pin "1") (pinfunction "1_1") (pintype "passive"))
      (node (ref "U1") (pin "17") (pinfunction "XTAL2_17") (pintype "bidirectional"))
    )
    (net (code "62") (name "VCC") (class "Default")
      (node (ref "3V1") (pin "1") (pinfunction "VIN_1") (pintype "bidirectional"))
      (node (ref "C11") (pin "2") (pinfunction "2_2") (pintype "passive"))
      (node (ref "C12") (pin "2") (pinfunction "2_2") (pintype "passive"))
      (node (ref "C13") (pin "2") (pinfunction "2_2") (pintype "passive"))
      (node (ref "C18") (pin "2") (pinfunction "2_2") (pintype "passive"))
      (node (ref "C19") (pin "2") (pinfunction "2_2") (pintype "passive"))
      (node (ref "C20") (pin "2") (pinfunction "2_2") (pintype "passive"))
      (node (ref "C21") (pin "A") (pinfunction "+_A") (pintype "passive"))
      (node (ref "C23") (pin "A") (pinfunction "+_A") (pintype "passive"))
      (node (ref "C30") (pin "2") (pinfunction "2_2") (pintype "passive"))
      (node (ref "C31") (pin "2") (pinfunction "2_2") (pintype "passive"))
      (node (ref "C32") (pin "2") (pinfunction "2_2") (pintype "passive"))
      (node (ref "C33") (pin "2") (pinfunction "2_2") (pintype "passive"))
      (node (ref "C34") (pin "2") (pinfunction "2_2") (pintype "passive"))
      (node (ref "C35") (pin "2") (pinfunction "2_2") (pintype "passive"))
      (node (ref "C42") (pin "1") (pinfunction "1_1") (pintype "passive"))
      (node (ref "C43") (pin "1") (pinfunction "1_1") (pintype "passive"))
      (node (ref "D1") (pin "C") (pinfunction "C_C") (pintype "passive"))
      (node (ref "L1") (pin "1") (pinfunction "1_1") (pintype "passive"))
      (node (ref "Q2") (pin "2") (pinfunction "E_2") (pintype "passive"))
      (node (ref "R10") (pin "2") (pinfunction "2_2") (pintype "passive"))
      (node (ref "R14") (pin "1") (pinfunction "1_1") (pintype "passive"))
      (node (ref "R7") (pin "2") (pinfunction "2_2") (pintype "passive"))
      (node (ref "U$1") (pin "100") (pinfunction "VDD_6_100") (pintype "bidirectional"))
      (node (ref "U$1") (pin "11") (pinfunction "VDD_1_11") (pintype "bidirectional"))
      (node (ref "U$1") (pin "19") (pinfunction "VDD_2_19") (pintype "bidirectional"))
      (node (ref "U$1") (pin "28") (pinfunction "VDD_3_28") (pintype "bidirectional"))
      (node (ref "U$1") (pin "50") (pinfunction "VDD_4_50") (pintype "bidirectional"))
      (node (ref "U$1") (pin "75") (pinfunction "VDD_5_75") (pintype "bidirectional"))
      (node (ref "U$2") (pin "20") (pinfunction "3V3_20") (pintype "bidirectional"))
      (node (ref "U$2") (pin "39") (pinfunction "IM1_39") (pintype "bidirectional"))
      (node (ref "U1") (pin "14") (pinfunction "IOVDD2_14") (pintype "bidirectional"))
      (node (ref "U1") (pin "19") (pinfunction "IOVDD3_19") (pintype "bidirectional"))
      (node (ref "U1") (pin "32") (pinfunction "TEST_32") (pintype "bidirectional"))
      (node (ref "U1") (pin "38") (pinfunction "AVDD1_38") (pintype "bidirectional"))
      (node (ref "U1") (pin "43") (pinfunction "AVDD2_43") (pintype "bidirectional"))
      (node (ref "U1") (pin "45") (pinfunction "AVDD3_45") (pintype "bidirectional"))
      (node (ref "U1") (pin "6") (pinfunction "IOVDD1_6") (pintype "bidirectional"))
    )
    (net (code "63") (name "VDD") (class "Default")
      (node (ref "C14") (pin "2") (pinfunction "2_2") (pintype "passive"))
      (node (ref "C15") (pin "2") (pinfunction "2_2") (pintype "passive"))
      (node (ref "C16") (pin "2") (pinfunction "2_2") (pintype "passive"))
      (node (ref "C17") (pin "2") (pinfunction "2_2") (pintype "passive"))
      (node (ref "C22") (pin "A") (pinfunction "+_A") (pintype "passive"))
      (node (ref "D2") (pin "C") (pinfunction "C_C") (pintype "passive"))
      (node (ref "U1") (pin "24") (pinfunction "CVDD3_24") (pintype "bidirectional"))
      (node (ref "U1") (pin "31") (pinfunction "CVDD4_31") (pintype "bidirectional"))
      (node (ref "U1") (pin "5") (pinfunction "CVDD1_5") (pintype "bidirectional"))
      (node (ref "U1") (pin "7") (pinfunction "CVDD2_7") (pintype "bidirectional"))
    )
    (net (code "64") (name "unconnected-(3V1-INH-Pad3)") (class "Default")
      (node (ref "3V1") (pin "3") (pinfunction "INH_3") (pintype "bidirectional"))
    )
    (net (code "65") (name "unconnected-(C22---PadC)") (class "Default")
      (node (ref "C22") (pin "C") (pinfunction "-_C") (pintype "passive"))
    )
    (net (code "66") (name "unconnected-(S1-1-PadA2)") (class "Default")
      (node (ref "S1") (pin "A2") (pinfunction "1_A2") (pintype "passive"))
    )
    (net (code "67") (name "unconnected-(S1-2-PadB2)") (class "Default")
      (node (ref "S1") (pin "B2") (pinfunction "2_B2") (pintype "passive"))
    )
    (net (code "68") (name "unconnected-(U$1-NRST-Pad14)") (class "Default")
      (node (ref "U$1") (pin "14") (pinfunction "NRST_14") (pintype "bidirectional"))
    )
    (net (code "69") (name "unconnected-(U$1-PA0{slash}ETH_MII_CRS{slash}ADC123_IN0(5T)-Pad23)") (class "Default")
      (node (ref "U$1") (pin "23") (pinfunction "PA0/ETH_MII_CRS/ADC123_IN0(5T)_23") (pintype "bidirectional"))
    )
    (net (code "70") (name "unconnected-(U$1-PA1{slash}ETH_RMII_RX_CLK{slash}ADC123_IN1(5T)-Pad24)") (class "Default")
      (node (ref "U$1") (pin "24") (pinfunction "PA1/ETH_RMII_RX_CLK/ADC123_IN1(5T)_24") (pintype "bidirectional"))
    )
    (net (code "71") (name "unconnected-(U$1-PA2{slash}ETH_MDIO{slash}ADC123_IN2(5T)-Pad25)") (class "Default")
      (node (ref "U$1") (pin "25") (pinfunction "PA2/ETH_MDIO/ADC123_IN2(5T)_25") (pintype "bidirectional"))
    )
    (net (code "72") (name "unconnected-(U$1-PA3{slash}ETH_MII_COL{slash}ADC123_IN2(5T)-Pad26)") (class "Default")
      (node (ref "U$1") (pin "26") (pinfunction "PA3/ETH_MII_COL/ADC123_IN2(5T)_26") (pintype "bidirectional"))
    )
    (net (code "73") (name "unconnected-(U$1-PA4{slash}ADC12_IN4-Pad29)") (class "Default")
      (node (ref "U$1") (pin "29") (pinfunction "PA4/ADC12_IN4_29") (pintype "bidirectional"))
    )
    (net (code "74") (name "unconnected-(U$1-PA5{slash}SPI1_SCK{slash}ADC12_IN5-Pad30)") (class "Default")
      (node (ref "U$1") (pin "30") (pinfunction "PA5/SPI1_SCK/ADC12_IN5_30") (pintype "bidirectional"))
    )
    (net (code "75") (name "unconnected-(U$1-PA6{slash}SPI1_MISO{slash}ADC12_IN6(5T)-Pad31)") (class "Default")
      (node (ref "U$1") (pin "31") (pinfunction "PA6/SPI1_MISO/ADC12_IN6(5T)_31") (pintype "bidirectional"))
    )
    (net (code "76") (name "unconnected-(U$1-PA7{slash}ETH_MII_RX_DV{slash}ADC12_IN7(5T)-Pad32)") (class "Default")
      (node (ref "U$1") (pin "32") (pinfunction "PA7/ETH_MII_RX_DV/ADC12_IN7(5T)_32") (pintype "bidirectional"))
    )
    (net (code "77") (name "unconnected-(U$1-PA8{slash}MCO1(5T)-Pad67)") (class "Default")
      (node (ref "U$1") (pin "67") (pinfunction "PA8/MCO1(5T)_67") (pintype "bidirectional"))
    )
    (net (code "78") (name "unconnected-(U$1-PA9{slash}USART1_TX(5T)-Pad68)") (class "Default")
      (node (ref "U$1") (pin "68") (pinfunction "PA9/USART1_TX(5T)_68") (pintype "bidirectional"))
    )
    (net (code "79") (name "unconnected-(U$1-PA10{slash}USART1_RX(5T)-Pad69)") (class "Default")
      (node (ref "U$1") (pin "69") (pinfunction "PA10/USART1_RX(5T)_69") (pintype "bidirectional"))
    )
    (net (code "80") (name "unconnected-(U$1-PA11{slash}USART1_CTS(5T)-Pad70)") (class "Default")
      (node (ref "U$1") (pin "70") (pinfunction "PA11/USART1_CTS(5T)_70") (pintype "bidirectional"))
    )
    (net (code "81") (name "unconnected-(U$1-PA12{slash}USART1_RTS(5T)-Pad71)") (class "Default")
      (node (ref "U$1") (pin "71") (pinfunction "PA12/USART1_RTS(5T)_71") (pintype "bidirectional"))
    )
    (net (code "82") (name "unconnected-(U$1-PA13{slash}JTMS-SWDAT(5T)-Pad72)") (class "Default")
      (node (ref "U$1") (pin "72") (pinfunction "PA13/JTMS-SWDAT(5T)_72") (pintype "bidirectional"))
    )
    (net (code "83") (name "unconnected-(U$1-PA14{slash}JTCK-SWCLK(5T)-Pad76)") (class "Default")
      (node (ref "U$1") (pin "76") (pinfunction "PA14/JTCK-SWCLK(5T)_76") (pintype "bidirectional"))
    )
    (net (code "84") (name "unconnected-(U$1-PA15{slash}JTDI(5T)-Pad77)") (class "Default")
      (node (ref "U$1") (pin "77") (pinfunction "PA15/JTDI(5T)_77") (pintype "bidirectional"))
    )
    (net (code "85") (name "unconnected-(U$1-PB0{slash}ETH_MII_RXD2{slash}ADC12_IN8(5T)-Pad35)") (class "Default")
      (node (ref "U$1") (pin "35") (pinfunction "PB0/ETH_MII_RXD2/ADC12_IN8(5T)_35") (pintype "bidirectional"))
    )
    (net (code "86") (name "unconnected-(U$1-PB1{slash}ETH_MII_RXD3{slash}ADC12_IN9(5T)-Pad36)") (class "Default")
      (node (ref "U$1") (pin "36") (pinfunction "PB1/ETH_MII_RXD3/ADC12_IN9(5T)_36") (pintype "bidirectional"))
    )
    (net (code "87") (name "unconnected-(U$1-PB2{slash}BOOT1(5T)-Pad37)") (class "Default")
      (node (ref "U$1") (pin "37") (pinfunction "PB2/BOOT1(5T)_37") (pintype "bidirectional"))
    )
    (net (code "88") (name "unconnected-(U$1-PB3{slash}JTDO(5T)-Pad89)") (class "Default")
      (node (ref "U$1") (pin "89") (pinfunction "PB3/JTDO(5T)_89") (pintype "bidirectional"))
    )
    (net (code "89") (name "unconnected-(U$1-PB4{slash}JNTRST(5T)-Pad90)") (class "Default")
      (node (ref "U$1") (pin "90") (pinfunction "PB4/JNTRST(5T)_90") (pintype "bidirectional"))
    )
    (net (code "90") (name "unconnected-(U$1-PB5{slash}TIM3_CH2(5T)-Pad91)") (class "Default")
      (node (ref "U$1") (pin "91") (pinfunction "PB5/TIM3_CH2(5T)_91") (pintype "bidirectional"))
    )
    (net (code "91") (name "unconnected-(U$1-PB6{slash}I2C1_SCL(5T)-Pad92)") (class "Default")
      (node (ref "U$1") (pin "92") (pinfunction "PB6/I2C1_SCL(5T)_92") (pintype "bidirectional"))
    )
    (net (code "92") (name "unconnected-(U$1-PB7{slash}I2C1_SDA(5T)-Pad93)") (class "Default")
      (node (ref "U$1") (pin "93") (pinfunction "PB7/I2C1_SDA(5T)_93") (pintype "bidirectional"))
    )
    (net (code "93") (name "unconnected-(U$1-PB8{slash}TIM10_CH1(5T)-Pad95)") (class "Default")
      (node (ref "U$1") (pin "95") (pinfunction "PB8/TIM10_CH1(5T)_95") (pintype "bidirectional"))
    )
    (net (code "94") (name "unconnected-(U$1-PB9{slash}TIM11_CH1(5T)-Pad96)") (class "Default")
      (node (ref "U$1") (pin "96") (pinfunction "PB9/TIM11_CH1(5T)_96") (pintype "bidirectional"))
    )
    (net (code "95") (name "unconnected-(U$1-PC0{slash}ADC123_IN10(5T)-Pad15)") (class "Default")
      (node (ref "U$1") (pin "15") (pinfunction "PC0/ADC123_IN10(5T)_15") (pintype "bidirectional"))
    )
    (net (code "96") (name "unconnected-(U$1-PC1{slash}ETH_MDC{slash}ADC123_IN11(5T)-Pad16)") (class "Default")
      (node (ref "U$1") (pin "16") (pinfunction "PC1/ETH_MDC/ADC123_IN11(5T)_16") (pintype "bidirectional"))
    )
    (net (code "97") (name "unconnected-(U$1-PC2{slash}ETH_MII_TXD2{slash}ADC123_IN12(5T)-Pad17)") (class "Default")
      (node (ref "U$1") (pin "17") (pinfunction "PC2/ETH_MII_TXD2/ADC123_IN12(5T)_17") (pintype "bidirectional"))
    )
    (net (code "98") (name "unconnected-(U$1-PC3{slash}ETH_MII_TX_CLK{slash}ADC123_IN13(5T)-Pad18)") (class "Default")
      (node (ref "U$1") (pin "18") (pinfunction "PC3/ETH_MII_TX_CLK/ADC123_IN13(5T)_18") (pintype "bidirectional"))
    )
    (net (code "99") (name "unconnected-(U$1-PC4{slash}ETH_MII_RXD0{slash}ADC12_IN14(5T)-Pad33)") (class "Default")
      (node (ref "U$1") (pin "33") (pinfunction "PC4/ETH_MII_RXD0/ADC12_IN14(5T)_33") (pintype "bidirectional"))
    )
    (net (code "100") (name "unconnected-(U$1-PC5{slash}ETH_MII_RXD1{slash}ADC12_IN15(5T)-Pad34)") (class "Default")
      (node (ref "U$1") (pin "34") (pinfunction "PC5/ETH_MII_RXD1/ADC12_IN15(5T)_34") (pintype "bidirectional"))
    )
    (net (code "101") (name "unconnected-(U$1-PC8{slash}TIM8_CH3(5T)-Pad65)") (class "Default")
      (node (ref "U$1") (pin "65") (pinfunction "PC8/TIM8_CH3(5T)_65") (pintype "bidirectional"))
    )
    (net (code "102") (name "unconnected-(U$1-PD0{slash}CAN1_RX(5T)-Pad81)") (class "Default")
      (node (ref "U$1") (pin "81") (pinfunction "PD0/CAN1_RX(5T)_81") (pintype "bidirectional"))
    )
    (net (code "103") (name "unconnected-(U$1-PD1{slash}CAN1_TX(5T)-Pad82)") (class "Default")
      (node (ref "U$1") (pin "82") (pinfunction "PD1/CAN1_TX(5T)_82") (pintype "bidirectional"))
    )
    (net (code "104") (name "unconnected-(U$1-PD2{slash}UART5_RX(5T)-Pad83)") (class "Default")
      (node (ref "U$1") (pin "83") (pinfunction "PD2/UART5_RX(5T)_83") (pintype "bidirectional"))
    )
    (net (code "105") (name "unconnected-(U$1-PD3(5T)-Pad84)") (class "Default")
      (node (ref "U$1") (pin "84") (pinfunction "PD3(5T)_84") (pintype "bidirectional"))
    )
    (net (code "106") (name "unconnected-(U$1-PD4(5T)-Pad85)") (class "Default")
      (node (ref "U$1") (pin "85") (pinfunction "PD4(5T)_85") (pintype "bidirectional"))
    )
    (net (code "107") (name "unconnected-(U$1-PD5{slash}USART2_TX(5T)-Pad86)") (class "Default")
      (node (ref "U$1") (pin "86") (pinfunction "PD5/USART2_TX(5T)_86") (pintype "bidirectional"))
    )
    (net (code "108") (name "unconnected-(U$1-PD6{slash}USART2_RX(5T)-Pad87)") (class "Default")
      (node (ref "U$1") (pin "87") (pinfunction "PD6/USART2_RX(5T)_87") (pintype "bidirectional"))
    )
    (net (code "109") (name "unconnected-(U$1-PD7(5T)-Pad88)") (class "Default")
      (node (ref "U$1") (pin "88") (pinfunction "PD7(5T)_88") (pintype "bidirectional"))
    )
    (net (code "110") (name "unconnected-(U$1-PD8{slash}USART3_TX(5T)-Pad55)") (class "Default")
      (node (ref "U$1") (pin "55") (pinfunction "PD8/USART3_TX(5T)_55") (pintype "bidirectional"))
    )
    (net (code "111") (name "unconnected-(U$1-PD9{slash}USART3_RX(5T)-Pad56)") (class "Default")
      (node (ref "U$1") (pin "56") (pinfunction "PD9/USART3_RX(5T)_56") (pintype "bidirectional"))
    )
    (net (code "112") (name "unconnected-(U$1-PD10(5T)-Pad57)") (class "Default")
      (node (ref "U$1") (pin "57") (pinfunction "PD10(5T)_57") (pintype "bidirectional"))
    )
    (net (code "113") (name "unconnected-(U$1-PD11(5T)-Pad58)") (class "Default")
      (node (ref "U$1") (pin "58") (pinfunction "PD11(5T)_58") (pintype "bidirectional"))
    )
    (net (code "114") (name "unconnected-(U$1-PD12{slash}TIM4_CH1(5T)-Pad59)") (class "Default")
      (node (ref "U$1") (pin "59") (pinfunction "PD12/TIM4_CH1(5T)_59") (pintype "bidirectional"))
    )
    (net (code "115") (name "unconnected-(U$1-PD13{slash}TIM4_CH2(5T)-Pad60)") (class "Default")
      (node (ref "U$1") (pin "60") (pinfunction "PD13/TIM4_CH2(5T)_60") (pintype "bidirectional"))
    )
    (net (code "116") (name "unconnected-(U$1-PD14{slash}TIM4_CH3(5T)-Pad61)") (class "Default")
      (node (ref "U$1") (pin "61") (pinfunction "PD14/TIM4_CH3(5T)_61") (pintype "bidirectional"))
    )
    (net (code "117") (name "unconnected-(U$1-PD15{slash}TIM4_CH4(5T)-Pad62)") (class "Default")
      (node (ref "U$1") (pin "62") (pinfunction "PD15/TIM4_CH4(5T)_62") (pintype "bidirectional"))
    )
    (net (code "118") (name "unconnected-(U$1-PH0-OSC_IN(5T)-Pad12)") (class "Default")
      (node (ref "U$1") (pin "12") (pinfunction "PH0-OSC_IN(5T)_12") (pintype "bidirectional"))
    )
    (net (code "119") (name "unconnected-(U$1-PH1-OSC_OUT(5T)-Pad13)") (class "Default")
      (node (ref "U$1") (pin "13") (pinfunction "PH1-OSC_OUT(5T)_13") (pintype "bidirectional"))
    )
    (net (code "120") (name "unconnected-(U$1-VBAT-Pad6)") (class "Default")
      (node (ref "U$1") (pin "6") (pinfunction "VBAT_6") (pintype "bidirectional"))
    )
    (net (code "121") (name "unconnected-(U$2-FMARK-Pad17)") (class "Default")
      (node (ref "U$2") (pin "17") (pinfunction "FMARK_17") (pintype "bidirectional"))
    )
    (net (code "122") (name "unconnected-(U$2-SDO-Pad14)") (class "Default")
      (node (ref "U$2") (pin "14") (pinfunction "SDO_14") (pintype "bidirectional"))
    )
    (net (code "123") (name "unconnected-(U$2-X+-Pad18)") (class "Default")
      (node (ref "U$2") (pin "18") (pinfunction "X+_18") (pintype "bidirectional"))
    )
    (net (code "124") (name "unconnected-(U$2-X--Pad19)") (class "Default")
      (node (ref "U$2") (pin "19") (pinfunction "X-_19") (pintype "bidirectional"))
    )
    (net (code "125") (name "unconnected-(U$2-Y+-Pad23)") (class "Default")
      (node (ref "U$2") (pin "23") (pinfunction "Y+_23") (pintype "bidirectional"))
    )
    (net (code "126") (name "unconnected-(U$2-Y--Pad22)") (class "Default")
      (node (ref "U$2") (pin "22") (pinfunction "Y-_22") (pintype "bidirectional"))
    )
    (net (code "127") (name "unconnected-(U1-LINEIN-Pad48)") (class "Default")
      (node (ref "U1") (pin "48") (pinfunction "LINEIN_48") (pintype "bidirectional"))
    )
    (net (code "128") (name "unconnected-(U1-MICN-Pad2)") (class "Default")
      (node (ref "U1") (pin "2") (pinfunction "MICN_2") (pintype "bidirectional"))
    )
    (net (code "129") (name "unconnected-(U1-MICP-Pad1)") (class "Default")
      (node (ref "U1") (pin "1") (pinfunction "MICP_1") (pintype "bidirectional"))
    )
    (net (code "130") (name "unconnected-(U1-TX-Pad27)") (class "Default")
      (node (ref "U1") (pin "27") (pinfunction "TX_27") (pintype "bidirectional"))
    )
    (net (code "131") (name "unconnected-(U1-VCO-Pad15)") (class "Default")
      (node (ref "U1") (pin "15") (pinfunction "VCO_15") (pintype "bidirectional"))
    )
    (net (code "132") (name "unconnected-(U1-XRESET-Pad3)") (class "Default")
      (node (ref "U1") (pin "3") (pinfunction "XRESET_3") (pintype "bidirectional"))
    )
    (net (code "133") (name "unconnected-(X1-Pad3)") (class "Default")
      (node (ref "X1") (pin "3") (pinfunction "3_3") (pintype "passive"))
    )
    (net (code "134") (name "unconnected-(X1-Pad4)") (class "Default")
      (node (ref "X1") (pin "4") (pinfunction "4_4") (pintype "passive"))
    )
  )
)
